# EVK-IRIS-W1_MikroBuses.net
KiCad netlist of a schematic drawn in Altium Designer
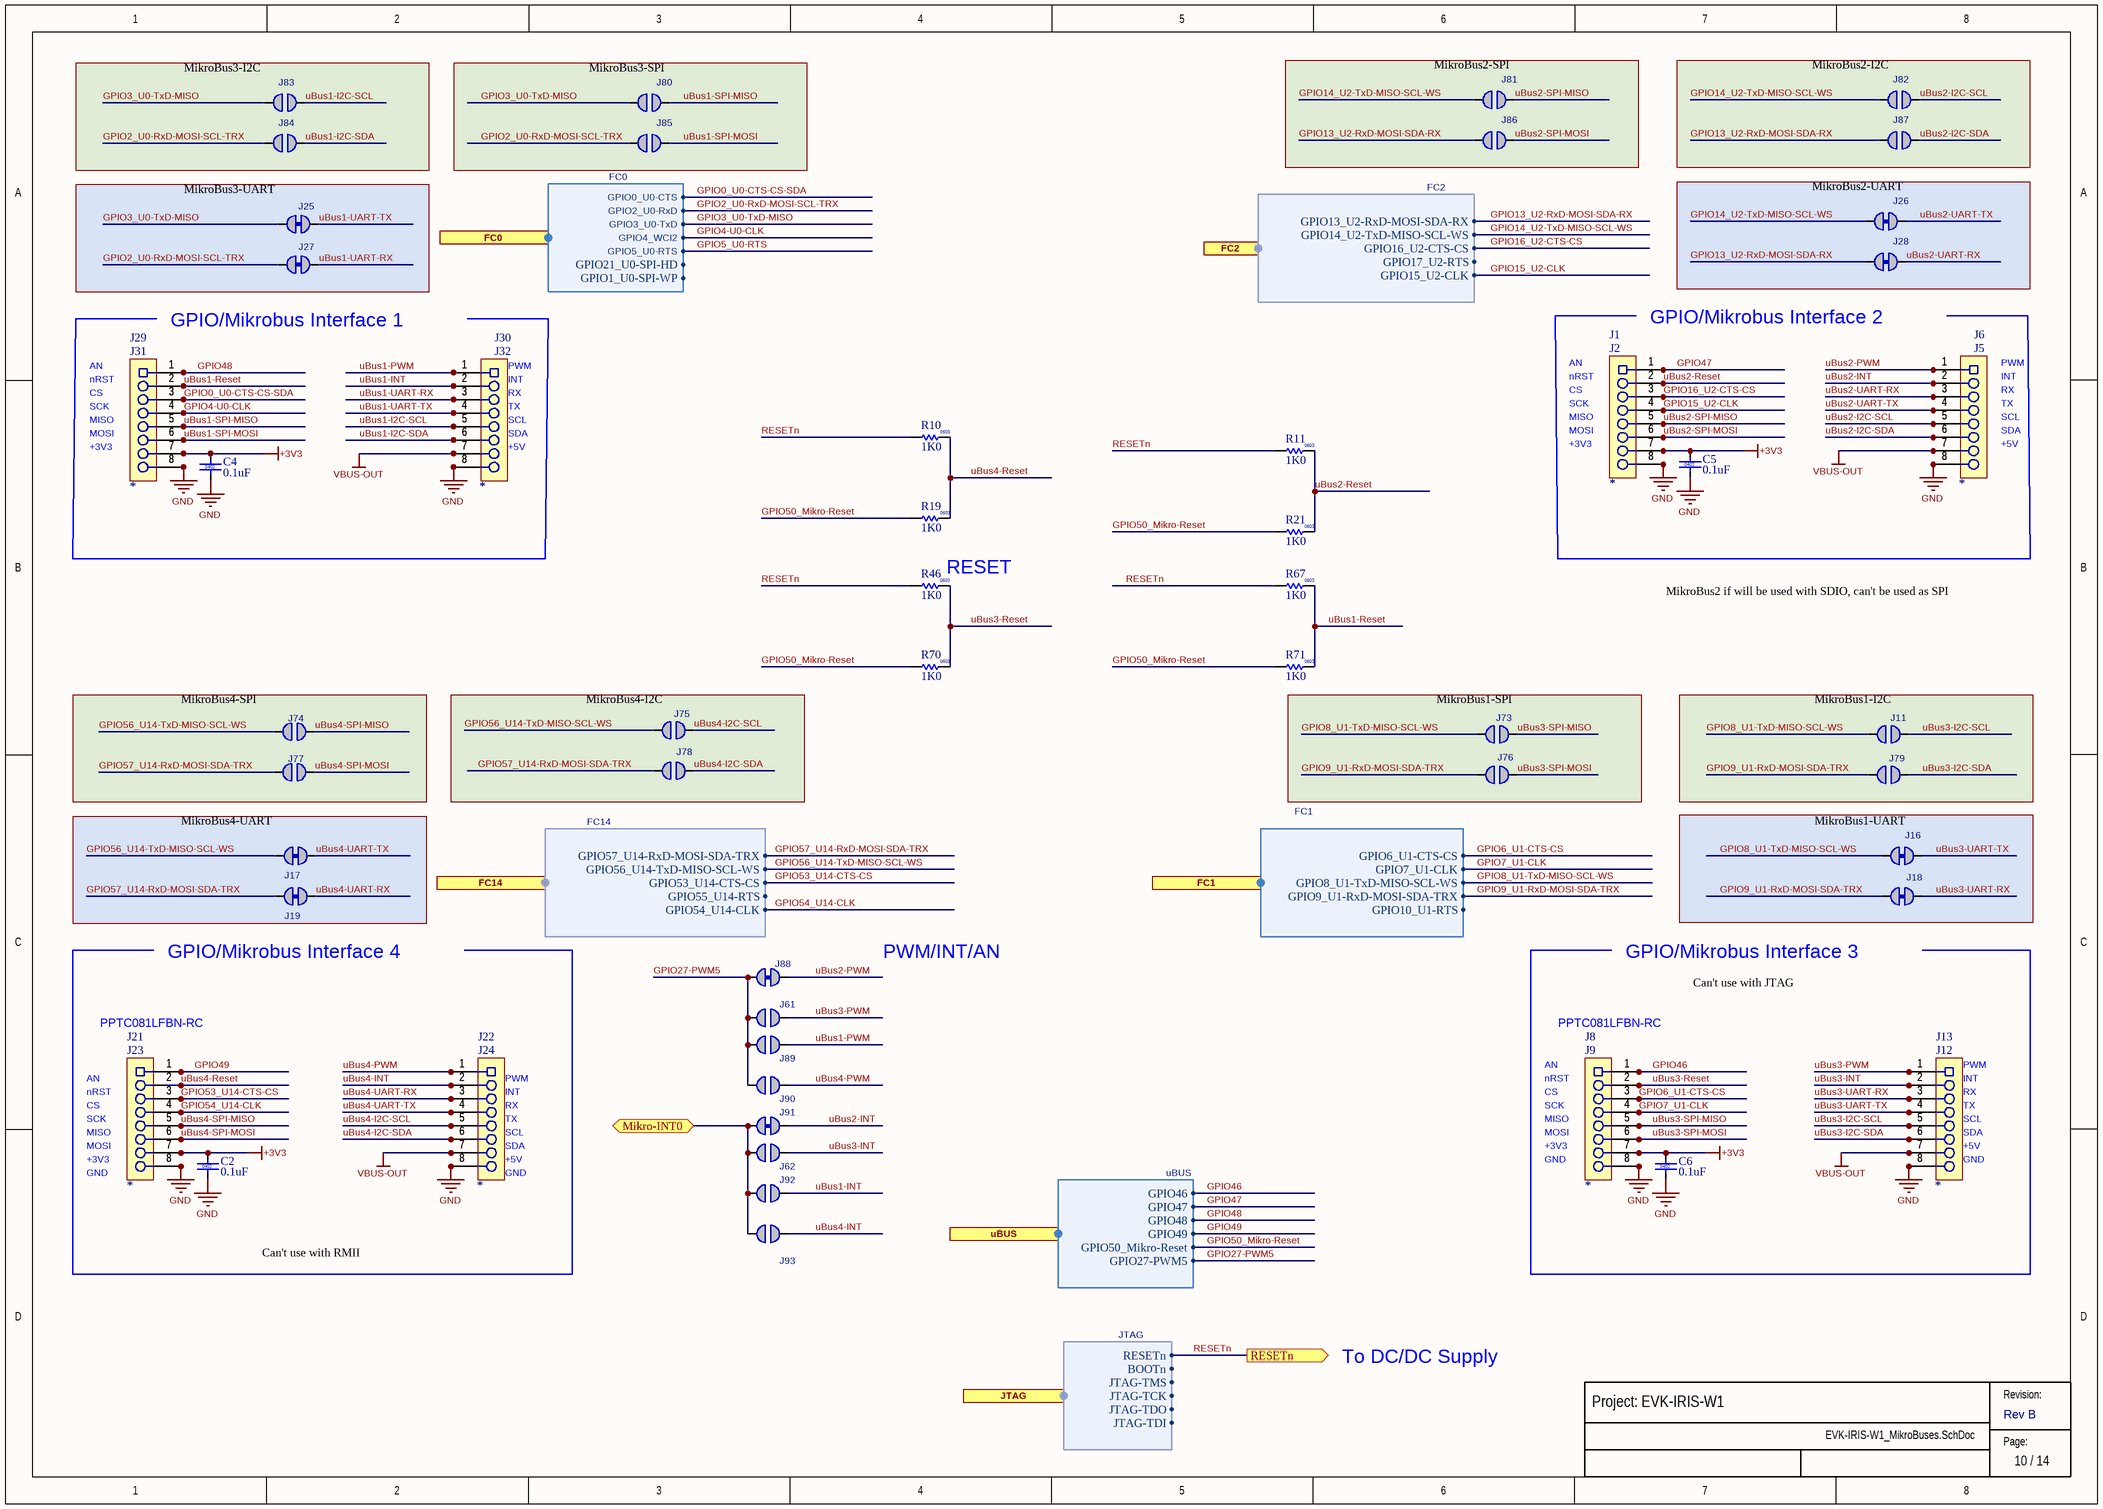
[diagram p0: EVK-IRIS-W1_MikroBuses.SchDoc]

(export (version "E")
  (design (tool "Eeschema 10.0.6"))
  (components
    (comp (ref "C2")
      (value "0.1uF")
      (footprint "Cap 0402 HD")
      (description "Cap, Ceramic 0.1uF 10V 10% X5R 0402")
      (fields
        (field (name "SIZE") "0402")
        (field (name "PART NUMBER") "120-00016")
        (field (name "TOLERANCE") "+/- 10%")
      )
      (libsource (lib "Arena_Parts_DB_Lib") (part "Cap Chip"))
    )
    (comp (ref "C4")
      (value "0.1uF")
      (footprint "Cap 0402 HD")
      (description "Cap, Ceramic 0.1uF 10V 10% X5R 0402")
      (fields
        (field (name "SIZE") "0402")
        (field (name "PART NUMBER") "120-00016")
        (field (name "TOLERANCE") "+/- 10%")
      )
      (libsource (lib "Arena_Parts_DB_Lib") (part "Cap Chip"))
    )
    (comp (ref "C5")
      (value "0.1uF")
      (footprint "Cap 0402 HD")
      (description "Cap, Ceramic 0.1uF 10V 10% X5R 0402")
      (fields
        (field (name "SIZE") "0402")
        (field (name "PART NUMBER") "120-00016")
        (field (name "TOLERANCE") "+/- 10%")
      )
      (libsource (lib "Arena_Parts_DB_Lib") (part "Cap Chip"))
    )
    (comp (ref "C6")
      (value "0.1uF")
      (footprint "Cap 0402 HD")
      (description "Cap, Ceramic 0.1uF 10V 10% X5R 0402")
      (fields
        (field (name "SIZE") "0402")
        (field (name "PART NUMBER") "120-00016")
        (field (name "TOLERANCE") "+/- 10%")
      )
      (libsource (lib "Arena_Parts_DB_Lib") (part "Cap Chip"))
    )
    (comp (ref "J1")
      (value "PPTC081LFBN-RC")
      (footprint "SKT-0.1P-8PIN-8x1_TH")
      (description "Socket, 0.100\" Pitch, 8 Pin, Vert TH, Black")
      (fields (field (name "VOLTAGE") "None") (field (name "MANUFACTURER P/N") "*"))
      (libsource (lib "PPTC081LFBN-RC") (part "PPTC081LFBN-RC"))
    )
    (comp (ref "J2")
      (value "PPTC081LFBN-RC")
      (footprint "SKT-0.1P-8PIN-8x1_TH")
      (description "Socket, 0.100\" Pitch, 8 Pin, Vert TH, Black")
      (fields (field (name "VOLTAGE") "None") (field (name "MANUFACTURER P/N") "*"))
      (libsource (lib "PPTC081LFBN-RC") (part "PPTC081LFBN-RC"))
    )
    (comp (ref "J5")
      (value "PPTC081LFBN-RC")
      (footprint "SKT-0.1P-8PIN-8x1_TH")
      (description "Socket, 0.100\" Pitch, 8 Pin, Vert TH, Black")
      (fields (field (name "VOLTAGE") "None") (field (name "MANUFACTURER P/N") "*"))
      (libsource (lib "") (part "PPTC081LFBN-RC_1"))
    )
    (comp (ref "J6")
      (value "PPTC081LFBN-RC")
      (footprint "SKT-0.1P-8PIN-8x1_TH")
      (description "Socket, 0.100\" Pitch, 8 Pin, Vert TH, Black")
      (fields (field (name "VOLTAGE") "None") (field (name "MANUFACTURER P/N") "*"))
      (libsource (lib "") (part "PPTC081LFBN-RC_1"))
    )
    (comp (ref "J8")
      (value "PPTC081LFBN-RC")
      (footprint "SKT-0.1P-8PIN-8x1_TH")
      (description "Socket, 0.100\" Pitch, 8 Pin, Vert TH, Black")
      (fields (field (name "VOLTAGE") "None") (field (name "MANUFACTURER P/N") "*"))
      (libsource (lib "PPTC081LFBN-RC") (part "PPTC081LFBN-RC"))
    )
    (comp (ref "J9")
      (value "PPTC081LFBN-RC")
      (footprint "SKT-0.1P-8PIN-8x1_TH")
      (description "Socket, 0.100\" Pitch, 8 Pin, Vert TH, Black")
      (fields (field (name "VOLTAGE") "None") (field (name "MANUFACTURER P/N") "*"))
      (libsource (lib "PPTC081LFBN-RC") (part "PPTC081LFBN-RC"))
    )
    (comp (ref "J11")
      (value "Solderbridge-OpenDNP")
      (footprint "Solderbridge-Open")
      (description "Solderbridge-Open")
      (fields (field (name "ADDED BY") "Paul B"))
      (libsource (lib "PCB_Misc") (part "Solderbridge-Open"))
    )
    (comp (ref "J12")
      (value "PPTC081LFBN-RC")
      (footprint "SKT-0.1P-8PIN-8x1_TH")
      (description "Socket, 0.100\" Pitch, 8 Pin, Vert TH, Black")
      (fields (field (name "VOLTAGE") "None") (field (name "MANUFACTURER P/N") "*"))
      (libsource (lib "") (part "PPTC081LFBN-RC_1"))
    )
    (comp (ref "J13")
      (value "PPTC081LFBN-RC")
      (footprint "SKT-0.1P-8PIN-8x1_TH")
      (description "Socket, 0.100\" Pitch, 8 Pin, Vert TH, Black")
      (fields (field (name "VOLTAGE") "None") (field (name "MANUFACTURER P/N") "*"))
      (libsource (lib "") (part "PPTC081LFBN-RC_1"))
    )
    (comp (ref "J16")
      (value "Solderbridge-ShortDNP")
      (footprint "Solderbridge-Short")
      (description "Solderbridge-Short")
      (fields (field (name "ADDED BY") "Paul B"))
      (libsource (lib "PCB_Misc") (part "Solderbridge-Short"))
    )
    (comp (ref "J17")
      (value "Solderbridge-ShortDNP")
      (footprint "Solderbridge-Short")
      (description "Solderbridge-Short")
      (fields (field (name "ADDED BY") "Paul B"))
      (libsource (lib "PCB_Misc") (part "Solderbridge-Short"))
    )
    (comp (ref "J18")
      (value "Solderbridge-ShortDNP")
      (footprint "Solderbridge-Short")
      (description "Solderbridge-Short")
      (fields (field (name "ADDED BY") "Paul B"))
      (libsource (lib "PCB_Misc") (part "Solderbridge-Short"))
    )
    (comp (ref "J19")
      (value "Solderbridge-ShortDNP")
      (footprint "Solderbridge-Short")
      (description "Solderbridge-Short")
      (fields (field (name "ADDED BY") "Paul B"))
      (libsource (lib "PCB_Misc") (part "Solderbridge-Short"))
    )
    (comp (ref "J21")
      (value "PPTC081LFBN-RC")
      (footprint "SKT-0.1P-8PIN-8x1_TH")
      (description "Socket, 0.100\" Pitch, 8 Pin, Vert TH, Black")
      (fields (field (name "VOLTAGE") "None") (field (name "MANUFACTURER P/N") "*"))
      (libsource (lib "PPTC081LFBN-RC") (part "PPTC081LFBN-RC"))
    )
    (comp (ref "J22")
      (value "PPTC081LFBN-RC")
      (footprint "SKT-0.1P-8PIN-8x1_TH")
      (description "Socket, 0.100\" Pitch, 8 Pin, Vert TH, Black")
      (fields (field (name "VOLTAGE") "None") (field (name "MANUFACTURER P/N") "*"))
      (libsource (lib "") (part "PPTC081LFBN-RC_1"))
    )
    (comp (ref "J23")
      (value "PPTC081LFBN-RC")
      (footprint "SKT-0.1P-8PIN-8x1_TH")
      (description "Socket, 0.100\" Pitch, 8 Pin, Vert TH, Black")
      (fields (field (name "VOLTAGE") "None") (field (name "MANUFACTURER P/N") "*"))
      (libsource (lib "PPTC081LFBN-RC") (part "PPTC081LFBN-RC"))
    )
    (comp (ref "J24")
      (value "PPTC081LFBN-RC")
      (footprint "SKT-0.1P-8PIN-8x1_TH")
      (description "Socket, 0.100\" Pitch, 8 Pin, Vert TH, Black")
      (fields (field (name "VOLTAGE") "None") (field (name "MANUFACTURER P/N") "*"))
      (libsource (lib "") (part "PPTC081LFBN-RC_1"))
    )
    (comp (ref "J25")
      (value "Solderbridge-ShortDNP")
      (footprint "Solderbridge-Short")
      (description "Solderbridge-Short")
      (fields (field (name "ADDED BY") "Paul B"))
      (libsource (lib "PCB_Misc") (part "Solderbridge-Short"))
    )
    (comp (ref "J26")
      (value "Solderbridge-ShortDNP")
      (footprint "Solderbridge-Short")
      (description "Solderbridge-Short")
      (fields (field (name "ADDED BY") "Paul B"))
      (libsource (lib "PCB_Misc") (part "Solderbridge-Short"))
    )
    (comp (ref "J27")
      (value "Solderbridge-ShortDNP")
      (footprint "Solderbridge-Short")
      (description "Solderbridge-Short")
      (fields (field (name "ADDED BY") "Paul B"))
      (libsource (lib "PCB_Misc") (part "Solderbridge-Short"))
    )
    (comp (ref "J28")
      (value "Solderbridge-ShortDNP")
      (footprint "Solderbridge-Short")
      (description "Solderbridge-Short")
      (fields (field (name "ADDED BY") "Paul B"))
      (libsource (lib "PCB_Misc") (part "Solderbridge-Short"))
    )
    (comp (ref "J29")
      (value "PPTC081LFBN-RC")
      (footprint "SKT-0.1P-8PIN-8x1_TH")
      (description "Socket, 0.100\" Pitch, 8 Pin, Vert TH, Black")
      (fields (field (name "VOLTAGE") "None") (field (name "MANUFACTURER P/N") "*"))
      (libsource (lib "PPTC081LFBN-RC") (part "PPTC081LFBN-RC"))
    )
    (comp (ref "J30")
      (value "PPTC081LFBN-RC")
      (footprint "SKT-0.1P-8PIN-8x1_TH")
      (description "Socket, 0.100\" Pitch, 8 Pin, Vert TH, Black")
      (fields (field (name "VOLTAGE") "None") (field (name "MANUFACTURER P/N") "*"))
      (libsource (lib "") (part "PPTC081LFBN-RC_1"))
    )
    (comp (ref "J31")
      (value "PPTC081LFBN-RC")
      (footprint "SKT-0.1P-8PIN-8x1_TH")
      (description "Socket, 0.100\" Pitch, 8 Pin, Vert TH, Black")
      (fields (field (name "VOLTAGE") "None") (field (name "MANUFACTURER P/N") "*"))
      (libsource (lib "PPTC081LFBN-RC") (part "PPTC081LFBN-RC"))
    )
    (comp (ref "J32")
      (value "PPTC081LFBN-RC")
      (footprint "SKT-0.1P-8PIN-8x1_TH")
      (description "Socket, 0.100\" Pitch, 8 Pin, Vert TH, Black")
      (fields (field (name "VOLTAGE") "None") (field (name "MANUFACTURER P/N") "*"))
      (libsource (lib "") (part "PPTC081LFBN-RC_1"))
    )
    (comp (ref "J61")
      (value "Solderbridge-OpenDNP")
      (footprint "Solderbridge-Open")
      (description "Solderbridge-Open")
      (fields (field (name "ADDED BY") "Paul B"))
      (libsource (lib "PCB_Misc") (part "Solderbridge-Open"))
    )
    (comp (ref "J62")
      (value "Solderbridge-OpenDNP")
      (footprint "Solderbridge-Open")
      (description "Solderbridge-Open")
      (fields (field (name "ADDED BY") "Paul B"))
      (libsource (lib "PCB_Misc") (part "Solderbridge-Open"))
    )
    (comp (ref "J73")
      (value "Solderbridge-OpenDNP")
      (footprint "Solderbridge-Open")
      (description "Solderbridge-Open")
      (fields (field (name "ADDED BY") "Paul B"))
      (libsource (lib "PCB_Misc") (part "Solderbridge-Open"))
    )
    (comp (ref "J74")
      (value "Solderbridge-OpenDNP")
      (footprint "Solderbridge-Open")
      (description "Solderbridge-Open")
      (fields (field (name "ADDED BY") "Paul B"))
      (libsource (lib "PCB_Misc") (part "Solderbridge-Open"))
    )
    (comp (ref "J75")
      (value "Solderbridge-OpenDNP")
      (footprint "Solderbridge-Open")
      (description "Solderbridge-Open")
      (fields (field (name "ADDED BY") "Paul B"))
      (libsource (lib "PCB_Misc") (part "Solderbridge-Open"))
    )
    (comp (ref "J76")
      (value "Solderbridge-OpenDNP")
      (footprint "Solderbridge-Open")
      (description "Solderbridge-Open")
      (fields (field (name "ADDED BY") "Paul B"))
      (libsource (lib "PCB_Misc") (part "Solderbridge-Open"))
    )
    (comp (ref "J77")
      (value "Solderbridge-OpenDNP")
      (footprint "Solderbridge-Open")
      (description "Solderbridge-Open")
      (fields (field (name "ADDED BY") "Paul B"))
      (libsource (lib "PCB_Misc") (part "Solderbridge-Open"))
    )
    (comp (ref "J78")
      (value "Solderbridge-OpenDNP")
      (footprint "Solderbridge-Open")
      (description "Solderbridge-Open")
      (fields (field (name "ADDED BY") "Paul B"))
      (libsource (lib "PCB_Misc") (part "Solderbridge-Open"))
    )
    (comp (ref "J79")
      (value "Solderbridge-OpenDNP")
      (footprint "Solderbridge-Open")
      (description "Solderbridge-Open")
      (fields (field (name "ADDED BY") "Paul B"))
      (libsource (lib "PCB_Misc") (part "Solderbridge-Open"))
    )
    (comp (ref "J80")
      (value "Solderbridge-OpenDNP")
      (footprint "Solderbridge-Open")
      (description "Solderbridge-Open")
      (fields (field (name "ADDED BY") "Paul B"))
      (libsource (lib "PCB_Misc") (part "Solderbridge-Open"))
    )
    (comp (ref "J81")
      (value "Solderbridge-OpenDNP")
      (footprint "Solderbridge-Open")
      (description "Solderbridge-Open")
      (fields (field (name "ADDED BY") "Paul B"))
      (libsource (lib "PCB_Misc") (part "Solderbridge-Open"))
    )
    (comp (ref "J82")
      (value "Solderbridge-OpenDNP")
      (footprint "Solderbridge-Open")
      (description "Solderbridge-Open")
      (fields (field (name "ADDED BY") "Paul B"))
      (libsource (lib "PCB_Misc") (part "Solderbridge-Open"))
    )
    (comp (ref "J83")
      (value "Solderbridge-OpenDNP")
      (footprint "Solderbridge-Open")
      (description "Solderbridge-Open")
      (fields (field (name "ADDED BY") "Paul B"))
      (libsource (lib "PCB_Misc") (part "Solderbridge-Open"))
    )
    (comp (ref "J84")
      (value "Solderbridge-OpenDNP")
      (footprint "Solderbridge-Open")
      (description "Solderbridge-Open")
      (fields (field (name "ADDED BY") "Paul B"))
      (libsource (lib "PCB_Misc") (part "Solderbridge-Open"))
    )
    (comp (ref "J85")
      (value "Solderbridge-OpenDNP")
      (footprint "Solderbridge-Open")
      (description "Solderbridge-Open")
      (fields (field (name "ADDED BY") "Paul B"))
      (libsource (lib "PCB_Misc") (part "Solderbridge-Open"))
    )
    (comp (ref "J86")
      (value "Solderbridge-OpenDNP")
      (footprint "Solderbridge-Open")
      (description "Solderbridge-Open")
      (fields (field (name "ADDED BY") "Paul B"))
      (libsource (lib "PCB_Misc") (part "Solderbridge-Open"))
    )
    (comp (ref "J87")
      (value "Solderbridge-OpenDNP")
      (footprint "Solderbridge-Open")
      (description "Solderbridge-Open")
      (fields (field (name "ADDED BY") "Paul B"))
      (libsource (lib "PCB_Misc") (part "Solderbridge-Open"))
    )
    (comp (ref "J88")
      (value "Solderbridge-ShortDNP")
      (footprint "Solderbridge-Short")
      (description "Solderbridge-Short")
      (fields (field (name "ADDED BY") "Paul B"))
      (libsource (lib "PCB_Misc") (part "Solderbridge-Short"))
    )
    (comp (ref "J89")
      (value "Solderbridge-OpenDNP")
      (footprint "Solderbridge-Open")
      (description "Solderbridge-Open")
      (fields (field (name "ADDED BY") "Paul B"))
      (libsource (lib "PCB_Misc") (part "Solderbridge-Open"))
    )
    (comp (ref "J90")
      (value "Solderbridge-OpenDNP")
      (footprint "Solderbridge-Open")
      (description "Solderbridge-Open")
      (fields (field (name "ADDED BY") "Paul B"))
      (libsource (lib "PCB_Misc") (part "Solderbridge-Open"))
    )
    (comp (ref "J91")
      (value "Solderbridge-ShortDNP")
      (footprint "Solderbridge-Short")
      (description "Solderbridge-Short")
      (fields (field (name "ADDED BY") "Paul B"))
      (libsource (lib "PCB_Misc") (part "Solderbridge-Short"))
    )
    (comp (ref "J92")
      (value "Solderbridge-OpenDNP")
      (footprint "Solderbridge-Open")
      (description "Solderbridge-Open")
      (fields (field (name "ADDED BY") "Paul B"))
      (libsource (lib "PCB_Misc") (part "Solderbridge-Open"))
    )
    (comp (ref "J93")
      (value "Solderbridge-OpenDNP")
      (footprint "Solderbridge-Open")
      (description "Solderbridge-Open")
      (fields (field (name "ADDED BY") "Paul B"))
      (libsource (lib "PCB_Misc") (part "Solderbridge-Open"))
    )
    (comp (ref "R10")
      (value "1K0")
      (footprint "RES 0603 HD")
      (description "RES THICK FILM CHIP 0603 25PPM 1K0 0.1% 100mW")
      (fields
        (field (name "SIZE") "0603")
        (field (name "PART NUMBER") "UBXH18-0000400")
        (field (name "TOLERANCE") "0.1%")
        (field (name "EDITOR") "martin.kessel")
      )
      (libsource (lib "UBX_Parts_DB_Lib") (part "Res sm"))
    )
    (comp (ref "R11")
      (value "1K0")
      (footprint "RES 0603 HD")
      (description "RES THICK FILM CHIP 0603 25PPM 1K0 0.1% 100mW")
      (fields
        (field (name "SIZE") "0603")
        (field (name "PART NUMBER") "UBXH18-0000400")
        (field (name "TOLERANCE") "0.1%")
        (field (name "EDITOR") "martin.kessel")
      )
      (libsource (lib "UBX_Parts_DB_Lib") (part "Res sm"))
    )
    (comp (ref "R19")
      (value "1K0")
      (footprint "RES 0603 HD")
      (description "RES THICK FILM CHIP 0603 25PPM 1K0 0.1% 100mW")
      (fields
        (field (name "SIZE") "0603")
        (field (name "PART NUMBER") "UBXH18-0000400")
        (field (name "TOLERANCE") "0.1%")
        (field (name "EDITOR") "martin.kessel")
      )
      (libsource (lib "UBX_Parts_DB_Lib") (part "Res sm"))
    )
    (comp (ref "R21")
      (value "1K0")
      (footprint "RES 0603 HD")
      (description "RES THICK FILM CHIP 0603 25PPM 1K0 0.1% 100mW")
      (fields
        (field (name "SIZE") "0603")
        (field (name "PART NUMBER") "UBXH18-0000400")
        (field (name "TOLERANCE") "0.1%")
        (field (name "EDITOR") "martin.kessel")
      )
      (libsource (lib "UBX_Parts_DB_Lib") (part "Res sm"))
    )
    (comp (ref "R46")
      (value "1K0")
      (footprint "RES 0603 HD")
      (description "RES THICK FILM CHIP 0603 25PPM 1K0 0.1% 100mW")
      (fields
        (field (name "SIZE") "0603")
        (field (name "PART NUMBER") "UBXH18-0000400")
        (field (name "TOLERANCE") "0.1%")
        (field (name "EDITOR") "martin.kessel")
      )
      (libsource (lib "UBX_Parts_DB_Lib") (part "Res sm"))
    )
    (comp (ref "R67")
      (value "1K0")
      (footprint "RES 0603 HD")
      (description "RES THICK FILM CHIP 0603 25PPM 1K0 0.1% 100mW")
      (fields
        (field (name "SIZE") "0603")
        (field (name "PART NUMBER") "UBXH18-0000400")
        (field (name "TOLERANCE") "0.1%")
        (field (name "EDITOR") "martin.kessel")
      )
      (libsource (lib "UBX_Parts_DB_Lib") (part "Res sm"))
    )
    (comp (ref "R70")
      (value "1K0")
      (footprint "RES 0603 HD")
      (description "RES THICK FILM CHIP 0603 25PPM 1K0 0.1% 100mW")
      (fields
        (field (name "SIZE") "0603")
        (field (name "PART NUMBER") "UBXH18-0000400")
        (field (name "TOLERANCE") "0.1%")
        (field (name "EDITOR") "martin.kessel")
      )
      (libsource (lib "UBX_Parts_DB_Lib") (part "Res sm"))
    )
    (comp (ref "R71")
      (value "1K0")
      (footprint "RES 0603 HD")
      (description "RES THICK FILM CHIP 0603 25PPM 1K0 0.1% 100mW")
      (fields
        (field (name "SIZE") "0603")
        (field (name "PART NUMBER") "UBXH18-0000400")
        (field (name "TOLERANCE") "0.1%")
        (field (name "EDITOR") "martin.kessel")
      )
      (libsource (lib "UBX_Parts_DB_Lib") (part "Res sm"))
    )
  )
  (nets
    (net (code "7") (name "+3V3") (class "Default")
      (node (ref "C2") (pin "2") (pinfunction "2_2") (pintype "passive"))
      (node (ref "C4") (pin "2") (pinfunction "2_2") (pintype "passive"))
      (node (ref "C5") (pin "2") (pinfunction "2_2") (pintype "passive"))
      (node (ref "C6") (pin "2") (pinfunction "2_2") (pintype "passive"))
      (node (ref "J1") (pin "7") (pinfunction "7_7") (pintype "passive"))
      (node (ref "J2") (pin "7") (pinfunction "7_7") (pintype "passive"))
      (node (ref "J21") (pin "7") (pinfunction "7_7") (pintype "passive"))
      (node (ref "J23") (pin "7") (pinfunction "7_7") (pintype "passive"))
      (node (ref "J29") (pin "7") (pinfunction "7_7") (pintype "passive"))
      (node (ref "J31") (pin "7") (pinfunction "7_7") (pintype "passive"))
      (node (ref "J8") (pin "7") (pinfunction "7_7") (pintype "passive"))
      (node (ref "J9") (pin "7") (pinfunction "7_7") (pintype "passive"))
    )
    (net (code "8") (name "/GPIO0_U0-CTS-CS-SDA") (class "Default")
      (node (ref "J29") (pin "3") (pinfunction "3_3") (pintype "passive"))
      (node (ref "J31") (pin "3") (pinfunction "3_3") (pintype "passive"))
    )
    (net (code "9") (name "/GPIO2_U0-RxD-MOSI-SCL-TRX") (class "Default")
      (node (ref "J27") (pin "1") (pinfunction "1_1") (pintype "passive"))
      (node (ref "J84") (pin "1") (pinfunction "1_1") (pintype "passive"))
      (node (ref "J85") (pin "1") (pinfunction "1_1") (pintype "passive"))
    )
    (net (code "10") (name "/GPIO3_U0-TxD-MISO") (class "Default")
      (node (ref "J25") (pin "1") (pinfunction "1_1") (pintype "passive"))
      (node (ref "J80") (pin "1") (pinfunction "1_1") (pintype "passive"))
      (node (ref "J83") (pin "1") (pinfunction "1_1") (pintype "passive"))
    )
    (net (code "11") (name "/GPIO4-U0-CLK") (class "Default")
      (node (ref "J29") (pin "4") (pinfunction "4_4") (pintype "passive"))
      (node (ref "J31") (pin "4") (pinfunction "4_4") (pintype "passive"))
    )
    (net (code "13") (name "/GPIO6_U1-CTS-CS") (class "Default")
      (node (ref "J8") (pin "3") (pinfunction "3_3") (pintype "passive"))
      (node (ref "J9") (pin "3") (pinfunction "3_3") (pintype "passive"))
    )
    (net (code "14") (name "/GPIO7_U1-CLK") (class "Default")
      (node (ref "J8") (pin "4") (pinfunction "4_4") (pintype "passive"))
      (node (ref "J9") (pin "4") (pinfunction "4_4") (pintype "passive"))
    )
    (net (code "15") (name "/GPIO8_U1-TxD-MISO-SCL-WS") (class "Default")
      (node (ref "J11") (pin "1") (pinfunction "1_1") (pintype "passive"))
      (node (ref "J16") (pin "1") (pinfunction "1_1") (pintype "passive"))
      (node (ref "J73") (pin "1") (pinfunction "1_1") (pintype "passive"))
    )
    (net (code "16") (name "/GPIO9_U1-RxD-MOSI-SDA-TRX") (class "Default")
      (node (ref "J18") (pin "1") (pinfunction "1_1") (pintype "passive"))
      (node (ref "J76") (pin "1") (pinfunction "1_1") (pintype "passive"))
      (node (ref "J79") (pin "1") (pinfunction "1_1") (pintype "passive"))
    )
    (net (code "17") (name "/GPIO13_U2-RxD-MOSI-SDA-RX") (class "Default")
      (node (ref "J28") (pin "1") (pinfunction "1_1") (pintype "passive"))
      (node (ref "J86") (pin "1") (pinfunction "1_1") (pintype "passive"))
      (node (ref "J87") (pin "1") (pinfunction "1_1") (pintype "passive"))
    )
    (net (code "18") (name "/GPIO14_U2-TxD-MISO-SCL-WS") (class "Default")
      (node (ref "J26") (pin "1") (pinfunction "1_1") (pintype "passive"))
      (node (ref "J81") (pin "1") (pinfunction "1_1") (pintype "passive"))
      (node (ref "J82") (pin "1") (pinfunction "1_1") (pintype "passive"))
    )
    (net (code "19") (name "/GPIO15_U2-CLK") (class "Default")
      (node (ref "J1") (pin "4") (pinfunction "4_4") (pintype "passive"))
      (node (ref "J2") (pin "4") (pinfunction "4_4") (pintype "passive"))
    )
    (net (code "20") (name "/GPIO16_U2-CTS-CS") (class "Default")
      (node (ref "J1") (pin "3") (pinfunction "3_3") (pintype "passive"))
      (node (ref "J2") (pin "3") (pinfunction "3_3") (pintype "passive"))
    )
    (net (code "21") (name "/GPIO27-PWM5") (class "Default")
      (node (ref "J61") (pin "1") (pinfunction "1_1") (pintype "passive"))
      (node (ref "J88") (pin "1") (pinfunction "1_1") (pintype "passive"))
      (node (ref "J89") (pin "1") (pinfunction "1_1") (pintype "passive"))
      (node (ref "J90") (pin "1") (pinfunction "1_1") (pintype "passive"))
    )
    (net (code "22") (name "/GPIO46") (class "Default")
      (node (ref "J8") (pin "1") (pinfunction "1_1") (pintype "passive"))
      (node (ref "J9") (pin "1") (pinfunction "1_1") (pintype "passive"))
    )
    (net (code "23") (name "/GPIO47") (class "Default")
      (node (ref "J1") (pin "1") (pinfunction "1_1") (pintype "passive"))
      (node (ref "J2") (pin "1") (pinfunction "1_1") (pintype "passive"))
    )
    (net (code "24") (name "/GPIO48") (class "Default")
      (node (ref "J29") (pin "1") (pinfunction "1_1") (pintype "passive"))
      (node (ref "J31") (pin "1") (pinfunction "1_1") (pintype "passive"))
    )
    (net (code "25") (name "/GPIO49") (class "Default")
      (node (ref "J21") (pin "1") (pinfunction "1_1") (pintype "passive"))
      (node (ref "J23") (pin "1") (pinfunction "1_1") (pintype "passive"))
    )
    (net (code "26") (name "/GPIO50_Mikro-Reset") (class "Default")
      (node (ref "R19") (pin "1") (pinfunction "1_1") (pintype "passive"))
      (node (ref "R21") (pin "1") (pinfunction "1_1") (pintype "passive"))
      (node (ref "R70") (pin "1") (pinfunction "1_1") (pintype "passive"))
      (node (ref "R71") (pin "1") (pinfunction "1_1") (pintype "passive"))
    )
    (net (code "27") (name "/GPIO53_U14-CTS-CS") (class "Default")
      (node (ref "J21") (pin "3") (pinfunction "3_3") (pintype "passive"))
      (node (ref "J23") (pin "3") (pinfunction "3_3") (pintype "passive"))
    )
    (net (code "28") (name "/GPIO54_U14-CLK") (class "Default")
      (node (ref "J21") (pin "4") (pinfunction "4_4") (pintype "passive"))
      (node (ref "J23") (pin "4") (pinfunction "4_4") (pintype "passive"))
    )
    (net (code "29") (name "/GPIO56_U14-TxD-MISO-SCL-WS") (class "Default")
      (node (ref "J17") (pin "1") (pinfunction "1_1") (pintype "passive"))
      (node (ref "J74") (pin "1") (pinfunction "1_1") (pintype "passive"))
      (node (ref "J75") (pin "1") (pinfunction "1_1") (pintype "passive"))
    )
    (net (code "30") (name "/GPIO57_U14-RxD-MOSI-SDA-TRX") (class "Default")
      (node (ref "J19") (pin "1") (pinfunction "1_1") (pintype "passive"))
      (node (ref "J77") (pin "1") (pinfunction "1_1") (pintype "passive"))
      (node (ref "J78") (pin "1") (pinfunction "1_1") (pintype "passive"))
    )
    (net (code "31") (name "/Mikro-INT0") (class "Default")
      (node (ref "J62") (pin "1") (pinfunction "1_1") (pintype "passive"))
      (node (ref "J91") (pin "1") (pinfunction "1_1") (pintype "passive"))
      (node (ref "J92") (pin "1") (pinfunction "1_1") (pintype "passive"))
      (node (ref "J93") (pin "1") (pinfunction "1_1") (pintype "passive"))
    )
    (net (code "32") (name "/RESETn") (class "Default")
      (node (ref "R10") (pin "1") (pinfunction "1_1") (pintype "passive"))
      (node (ref "R11") (pin "1") (pinfunction "1_1") (pintype "passive"))
      (node (ref "R46") (pin "1") (pinfunction "1_1") (pintype "passive"))
      (node (ref "R67") (pin "1") (pinfunction "1_1") (pintype "passive"))
    )
    (net (code "33") (name "/uBus1-I2C-SCL") (class "Default")
      (node (ref "J30") (pin "5") (pinfunction "5_5") (pintype "passive"))
      (node (ref "J32") (pin "5") (pinfunction "5_5") (pintype "passive"))
      (node (ref "J83") (pin "2") (pinfunction "2_2") (pintype "passive"))
    )
    (net (code "34") (name "/uBus1-I2C-SDA") (class "Default")
      (node (ref "J30") (pin "6") (pinfunction "6_6") (pintype "passive"))
      (node (ref "J32") (pin "6") (pinfunction "6_6") (pintype "passive"))
      (node (ref "J84") (pin "2") (pinfunction "2_2") (pintype "passive"))
    )
    (net (code "35") (name "/uBus1-INT") (class "Default")
      (node (ref "J30") (pin "2") (pinfunction "2_2") (pintype "passive"))
      (node (ref "J32") (pin "2") (pinfunction "2_2") (pintype "passive"))
      (node (ref "J92") (pin "2") (pinfunction "2_2") (pintype "passive"))
    )
    (net (code "36") (name "/uBus1-PWM") (class "Default")
      (node (ref "J30") (pin "1") (pinfunction "1_1") (pintype "passive"))
      (node (ref "J32") (pin "1") (pinfunction "1_1") (pintype "passive"))
      (node (ref "J89") (pin "2") (pinfunction "2_2") (pintype "passive"))
    )
    (net (code "37") (name "/uBus1-Reset") (class "Default")
      (node (ref "J29") (pin "2") (pinfunction "2_2") (pintype "passive"))
      (node (ref "J31") (pin "2") (pinfunction "2_2") (pintype "passive"))
      (node (ref "R67") (pin "2") (pinfunction "2_2") (pintype "passive"))
      (node (ref "R71") (pin "2") (pinfunction "2_2") (pintype "passive"))
    )
    (net (code "38") (name "/uBus1-SPI-MISO") (class "Default")
      (node (ref "J29") (pin "5") (pinfunction "5_5") (pintype "passive"))
      (node (ref "J31") (pin "5") (pinfunction "5_5") (pintype "passive"))
      (node (ref "J80") (pin "2") (pinfunction "2_2") (pintype "passive"))
    )
    (net (code "39") (name "/uBus1-SPI-MOSI") (class "Default")
      (node (ref "J29") (pin "6") (pinfunction "6_6") (pintype "passive"))
      (node (ref "J31") (pin "6") (pinfunction "6_6") (pintype "passive"))
      (node (ref "J85") (pin "2") (pinfunction "2_2") (pintype "passive"))
    )
    (net (code "40") (name "/uBus1-UART-RX") (class "Default")
      (node (ref "J27") (pin "2") (pinfunction "2_2") (pintype "passive"))
      (node (ref "J30") (pin "3") (pinfunction "3_3") (pintype "passive"))
      (node (ref "J32") (pin "3") (pinfunction "3_3") (pintype "passive"))
    )
    (net (code "41") (name "/uBus1-UART-TX") (class "Default")
      (node (ref "J25") (pin "2") (pinfunction "2_2") (pintype "passive"))
      (node (ref "J30") (pin "4") (pinfunction "4_4") (pintype "passive"))
      (node (ref "J32") (pin "4") (pinfunction "4_4") (pintype "passive"))
    )
    (net (code "42") (name "/uBus2-I2C-SCL") (class "Default")
      (node (ref "J5") (pin "5") (pinfunction "5_5") (pintype "passive"))
      (node (ref "J6") (pin "5") (pinfunction "5_5") (pintype "passive"))
      (node (ref "J82") (pin "2") (pinfunction "2_2") (pintype "passive"))
    )
    (net (code "43") (name "/uBus2-I2C-SDA") (class "Default")
      (node (ref "J5") (pin "6") (pinfunction "6_6") (pintype "passive"))
      (node (ref "J6") (pin "6") (pinfunction "6_6") (pintype "passive"))
      (node (ref "J87") (pin "2") (pinfunction "2_2") (pintype "passive"))
    )
    (net (code "44") (name "/uBus2-INT") (class "Default")
      (node (ref "J5") (pin "2") (pinfunction "2_2") (pintype "passive"))
      (node (ref "J6") (pin "2") (pinfunction "2_2") (pintype "passive"))
      (node (ref "J91") (pin "2") (pinfunction "2_2") (pintype "passive"))
    )
    (net (code "45") (name "/uBus2-PWM") (class "Default")
      (node (ref "J5") (pin "1") (pinfunction "1_1") (pintype "passive"))
      (node (ref "J6") (pin "1") (pinfunction "1_1") (pintype "passive"))
      (node (ref "J88") (pin "2") (pinfunction "2_2") (pintype "passive"))
    )
    (net (code "46") (name "/uBus2-Reset") (class "Default")
      (node (ref "J1") (pin "2") (pinfunction "2_2") (pintype "passive"))
      (node (ref "J2") (pin "2") (pinfunction "2_2") (pintype "passive"))
      (node (ref "R11") (pin "2") (pinfunction "2_2") (pintype "passive"))
      (node (ref "R21") (pin "2") (pinfunction "2_2") (pintype "passive"))
    )
    (net (code "47") (name "/uBus2-SPI-MISO") (class "Default")
      (node (ref "J1") (pin "5") (pinfunction "5_5") (pintype "passive"))
      (node (ref "J2") (pin "5") (pinfunction "5_5") (pintype "passive"))
      (node (ref "J81") (pin "2") (pinfunction "2_2") (pintype "passive"))
    )
    (net (code "48") (name "/uBus2-SPI-MOSI") (class "Default")
      (node (ref "J1") (pin "6") (pinfunction "6_6") (pintype "passive"))
      (node (ref "J2") (pin "6") (pinfunction "6_6") (pintype "passive"))
      (node (ref "J86") (pin "2") (pinfunction "2_2") (pintype "passive"))
    )
    (net (code "49") (name "/uBus2-UART-RX") (class "Default")
      (node (ref "J28") (pin "2") (pinfunction "2_2") (pintype "passive"))
      (node (ref "J5") (pin "3") (pinfunction "3_3") (pintype "passive"))
      (node (ref "J6") (pin "3") (pinfunction "3_3") (pintype "passive"))
    )
    (net (code "50") (name "/uBus2-UART-TX") (class "Default")
      (node (ref "J26") (pin "2") (pinfunction "2_2") (pintype "passive"))
      (node (ref "J5") (pin "4") (pinfunction "4_4") (pintype "passive"))
      (node (ref "J6") (pin "4") (pinfunction "4_4") (pintype "passive"))
    )
    (net (code "51") (name "/uBus3-I2C-SCL") (class "Default")
      (node (ref "J11") (pin "2") (pinfunction "2_2") (pintype "passive"))
      (node (ref "J12") (pin "5") (pinfunction "5_5") (pintype "passive"))
      (node (ref "J13") (pin "5") (pinfunction "5_5") (pintype "passive"))
    )
    (net (code "52") (name "/uBus3-I2C-SDA") (class "Default")
      (node (ref "J12") (pin "6") (pinfunction "6_6") (pintype "passive"))
      (node (ref "J13") (pin "6") (pinfunction "6_6") (pintype "passive"))
      (node (ref "J79") (pin "2") (pinfunction "2_2") (pintype "passive"))
    )
    (net (code "53") (name "/uBus3-INT") (class "Default")
      (node (ref "J12") (pin "2") (pinfunction "2_2") (pintype "passive"))
      (node (ref "J13") (pin "2") (pinfunction "2_2") (pintype "passive"))
      (node (ref "J62") (pin "2") (pinfunction "2_2") (pintype "passive"))
    )
    (net (code "54") (name "/uBus3-PWM") (class "Default")
      (node (ref "J12") (pin "1") (pinfunction "1_1") (pintype "passive"))
      (node (ref "J13") (pin "1") (pinfunction "1_1") (pintype "passive"))
      (node (ref "J61") (pin "2") (pinfunction "2_2") (pintype "passive"))
    )
    (net (code "55") (name "/uBus3-Reset") (class "Default")
      (node (ref "J8") (pin "2") (pinfunction "2_2") (pintype "passive"))
      (node (ref "J9") (pin "2") (pinfunction "2_2") (pintype "passive"))
      (node (ref "R46") (pin "2") (pinfunction "2_2") (pintype "passive"))
      (node (ref "R70") (pin "2") (pinfunction "2_2") (pintype "passive"))
    )
    (net (code "56") (name "/uBus3-SPI-MISO") (class "Default")
      (node (ref "J73") (pin "2") (pinfunction "2_2") (pintype "passive"))
      (node (ref "J8") (pin "5") (pinfunction "5_5") (pintype "passive"))
      (node (ref "J9") (pin "5") (pinfunction "5_5") (pintype "passive"))
    )
    (net (code "57") (name "/uBus3-SPI-MOSI") (class "Default")
      (node (ref "J76") (pin "2") (pinfunction "2_2") (pintype "passive"))
      (node (ref "J8") (pin "6") (pinfunction "6_6") (pintype "passive"))
      (node (ref "J9") (pin "6") (pinfunction "6_6") (pintype "passive"))
    )
    (net (code "58") (name "/uBus3-UART-RX") (class "Default")
      (node (ref "J12") (pin "3") (pinfunction "3_3") (pintype "passive"))
      (node (ref "J13") (pin "3") (pinfunction "3_3") (pintype "passive"))
      (node (ref "J18") (pin "2") (pinfunction "2_2") (pintype "passive"))
    )
    (net (code "59") (name "/uBus3-UART-TX") (class "Default")
      (node (ref "J12") (pin "4") (pinfunction "4_4") (pintype "passive"))
      (node (ref "J13") (pin "4") (pinfunction "4_4") (pintype "passive"))
      (node (ref "J16") (pin "2") (pinfunction "2_2") (pintype "passive"))
    )
    (net (code "60") (name "/uBus4-I2C-SCL") (class "Default")
      (node (ref "J22") (pin "5") (pinfunction "5_5") (pintype "passive"))
      (node (ref "J24") (pin "5") (pinfunction "5_5") (pintype "passive"))
      (node (ref "J75") (pin "2") (pinfunction "2_2") (pintype "passive"))
    )
    (net (code "61") (name "/uBus4-I2C-SDA") (class "Default")
      (node (ref "J22") (pin "6") (pinfunction "6_6") (pintype "passive"))
      (node (ref "J24") (pin "6") (pinfunction "6_6") (pintype "passive"))
      (node (ref "J78") (pin "2") (pinfunction "2_2") (pintype "passive"))
    )
    (net (code "62") (name "/uBus4-INT") (class "Default")
      (node (ref "J22") (pin "2") (pinfunction "2_2") (pintype "passive"))
      (node (ref "J24") (pin "2") (pinfunction "2_2") (pintype "passive"))
      (node (ref "J93") (pin "2") (pinfunction "2_2") (pintype "passive"))
    )
    (net (code "63") (name "/uBus4-PWM") (class "Default")
      (node (ref "J22") (pin "1") (pinfunction "1_1") (pintype "passive"))
      (node (ref "J24") (pin "1") (pinfunction "1_1") (pintype "passive"))
      (node (ref "J90") (pin "2") (pinfunction "2_2") (pintype "passive"))
    )
    (net (code "64") (name "/uBus4-Reset") (class "Default")
      (node (ref "J21") (pin "2") (pinfunction "2_2") (pintype "passive"))
      (node (ref "J23") (pin "2") (pinfunction "2_2") (pintype "passive"))
      (node (ref "R10") (pin "2") (pinfunction "2_2") (pintype "passive"))
      (node (ref "R19") (pin "2") (pinfunction "2_2") (pintype "passive"))
    )
    (net (code "65") (name "/uBus4-SPI-MISO") (class "Default")
      (node (ref "J21") (pin "5") (pinfunction "5_5") (pintype "passive"))
      (node (ref "J23") (pin "5") (pinfunction "5_5") (pintype "passive"))
      (node (ref "J74") (pin "2") (pinfunction "2_2") (pintype "passive"))
    )
    (net (code "66") (name "/uBus4-SPI-MOSI") (class "Default")
      (node (ref "J21") (pin "6") (pinfunction "6_6") (pintype "passive"))
      (node (ref "J23") (pin "6") (pinfunction "6_6") (pintype "passive"))
      (node (ref "J77") (pin "2") (pinfunction "2_2") (pintype "passive"))
    )
    (net (code "67") (name "/uBus4-UART-RX") (class "Default")
      (node (ref "J19") (pin "2") (pinfunction "2_2") (pintype "passive"))
      (node (ref "J22") (pin "3") (pinfunction "3_3") (pintype "passive"))
      (node (ref "J24") (pin "3") (pinfunction "3_3") (pintype "passive"))
    )
    (net (code "68") (name "/uBus4-UART-TX") (class "Default")
      (node (ref "J17") (pin "2") (pinfunction "2_2") (pintype "passive"))
      (node (ref "J22") (pin "4") (pinfunction "4_4") (pintype "passive"))
      (node (ref "J24") (pin "4") (pinfunction "4_4") (pintype "passive"))
    )
    (net (code "75") (name "GND") (class "Default")
      (node (ref "C2") (pin "1") (pinfunction "1_1") (pintype "passive"))
      (node (ref "C4") (pin "1") (pinfunction "1_1") (pintype "passive"))
      (node (ref "C5") (pin "1") (pinfunction "1_1") (pintype "passive"))
      (node (ref "C6") (pin "1") (pinfunction "1_1") (pintype "passive"))
      (node (ref "J1") (pin "8") (pinfunction "8_8") (pintype "passive"))
      (node (ref "J12") (pin "8") (pinfunction "8_8") (pintype "passive"))
      (node (ref "J13") (pin "8") (pinfunction "8_8") (pintype "passive"))
      (node (ref "J2") (pin "8") (pinfunction "8_8") (pintype "passive"))
      (node (ref "J21") (pin "8") (pinfunction "8_8") (pintype "passive"))
      (node (ref "J22") (pin "8") (pinfunction "8_8") (pintype "passive"))
      (node (ref "J23") (pin "8") (pinfunction "8_8") (pintype "passive"))
      (node (ref "J24") (pin "8") (pinfunction "8_8") (pintype "passive"))
      (node (ref "J29") (pin "8") (pinfunction "8_8") (pintype "passive"))
      (node (ref "J30") (pin "8") (pinfunction "8_8") (pintype "passive"))
      (node (ref "J31") (pin "8") (pinfunction "8_8") (pintype "passive"))
      (node (ref "J32") (pin "8") (pinfunction "8_8") (pintype "passive"))
      (node (ref "J5") (pin "8") (pinfunction "8_8") (pintype "passive"))
      (node (ref "J6") (pin "8") (pinfunction "8_8") (pintype "passive"))
      (node (ref "J8") (pin "8") (pinfunction "8_8") (pintype "passive"))
      (node (ref "J9") (pin "8") (pinfunction "8_8") (pintype "passive"))
    )
    (net (code "76") (name "VBUS-OUT") (class "Default")
      (node (ref "J12") (pin "7") (pinfunction "7_7") (pintype "passive"))
      (node (ref "J13") (pin "7") (pinfunction "7_7") (pintype "passive"))
      (node (ref "J22") (pin "7") (pinfunction "7_7") (pintype "passive"))
      (node (ref "J24") (pin "7") (pinfunction "7_7") (pintype "passive"))
      (node (ref "J30") (pin "7") (pinfunction "7_7") (pintype "passive"))
      (node (ref "J32") (pin "7") (pinfunction "7_7") (pintype "passive"))
      (node (ref "J5") (pin "7") (pinfunction "7_7") (pintype "passive"))
      (node (ref "J6") (pin "7") (pinfunction "7_7") (pintype "passive"))
    )
  )
)
